# bpod_stepper_1_3.net
KiCad netlist of a schematic drawn in EAGLE
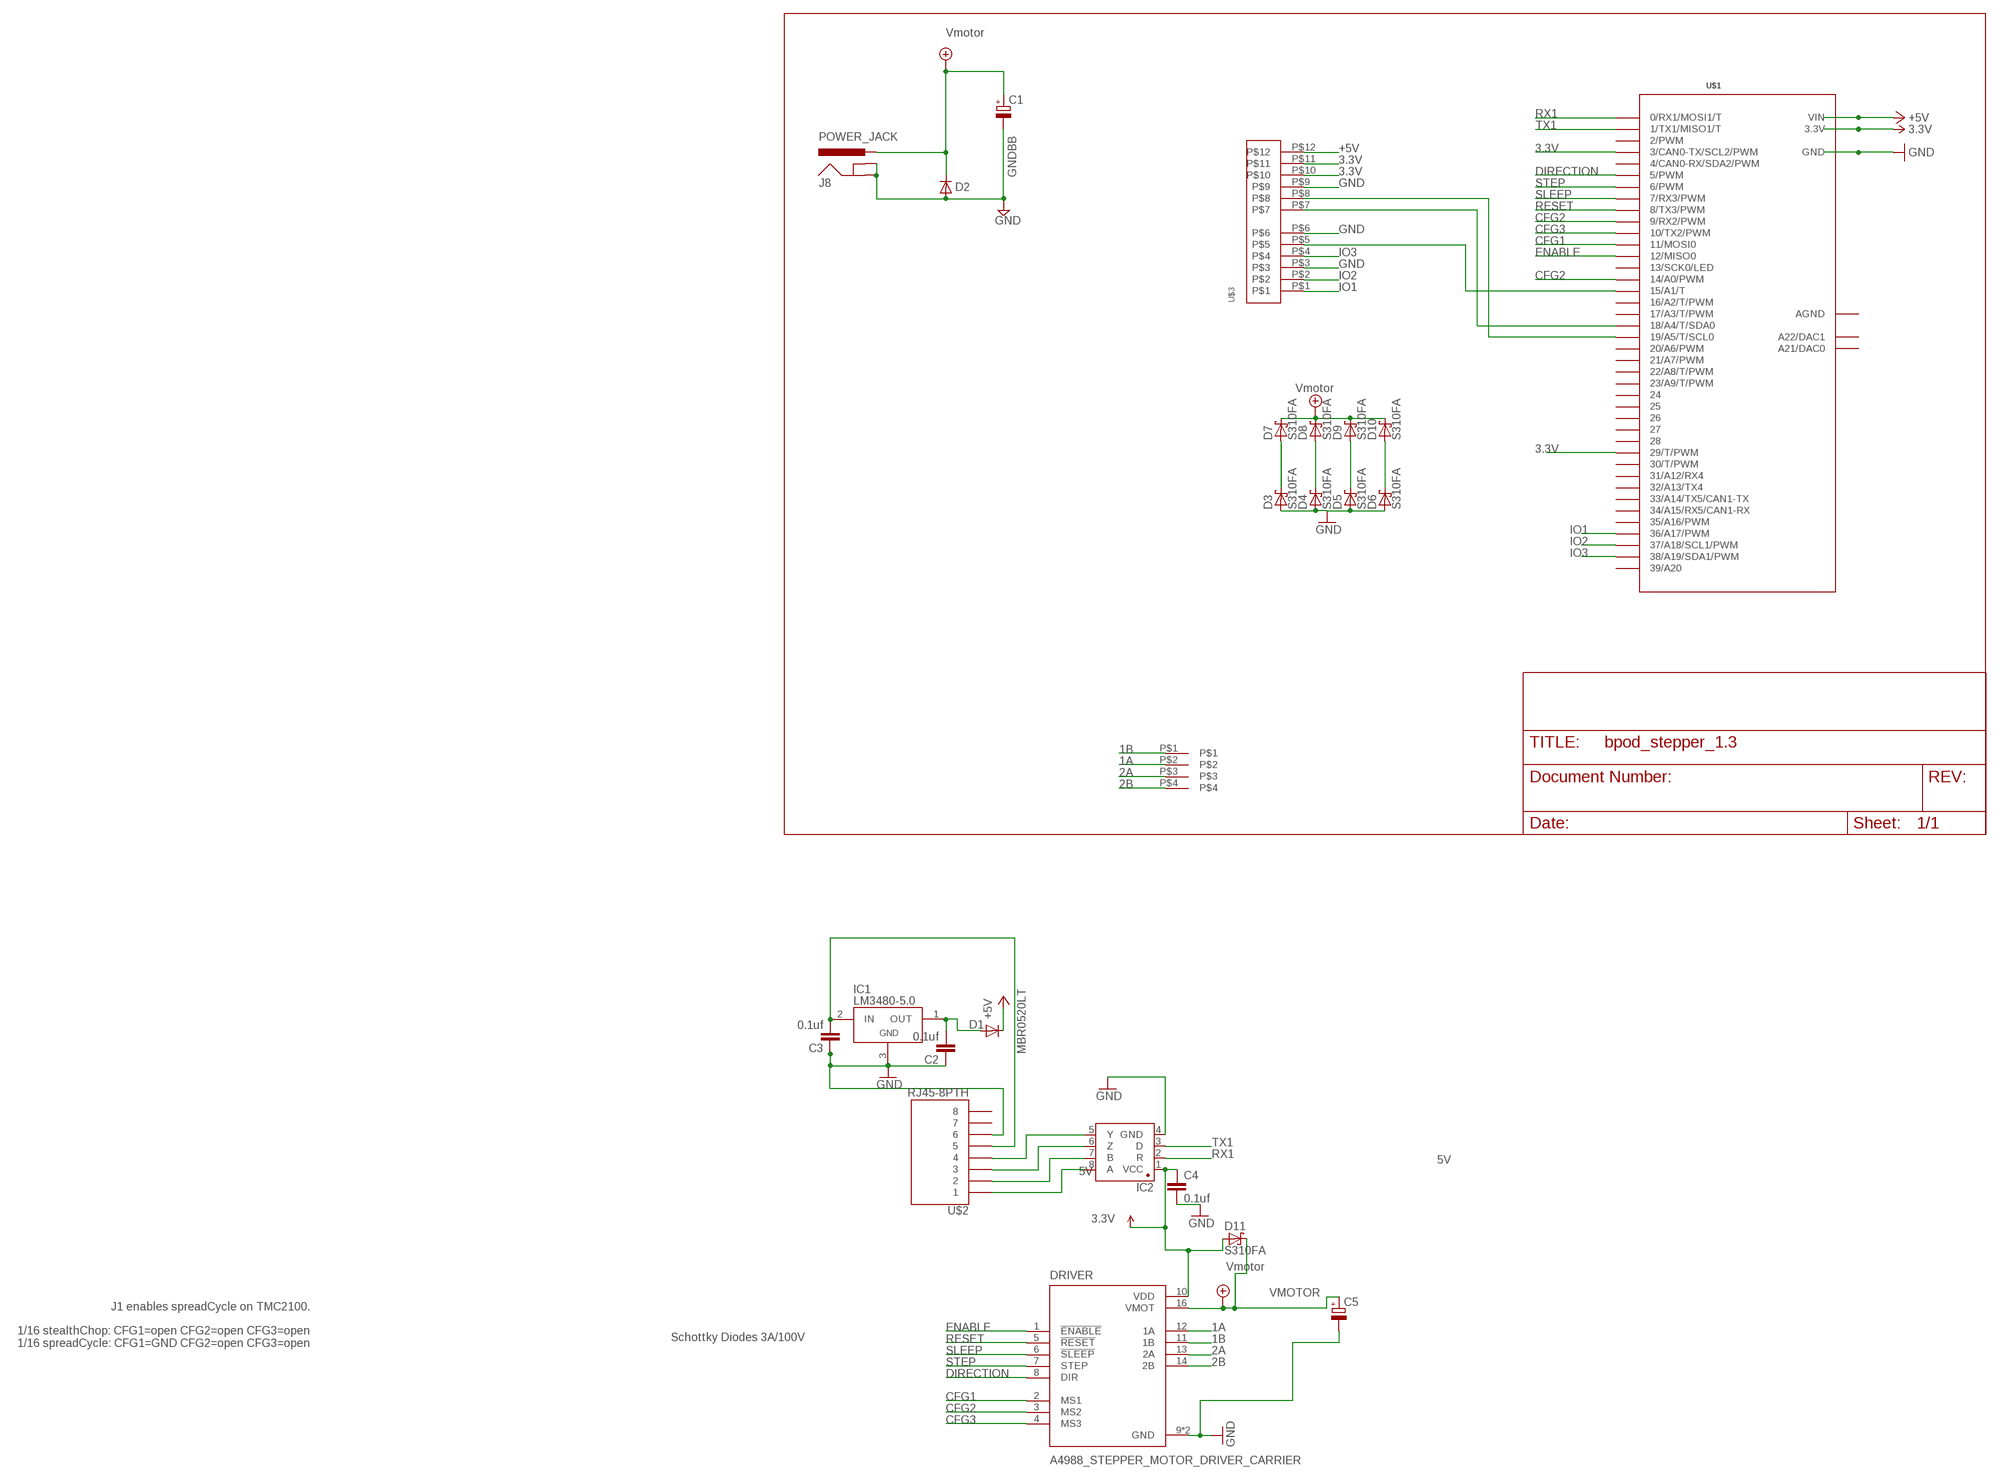
[diagram p0: schematic, sheet 1]

(export (version "E")
  (design (tool "Eeschema 10.0.6"))
  (components
    (comp (ref "C1")
      (value "CPOL-EUG")
      (footprint "eagle-import:PANASONIC_G")
      (libsource (lib "eagle-import") (part "CPOL-EUG"))
    )
    (comp (ref "C2")
      (value "0.1uf")
      (footprint "eagle-import:1206@1")
      (libsource (lib "eagle-import") (part "CAP1206"))
    )
    (comp (ref "C3")
      (value "0.1uf")
      (footprint "eagle-import:1206@1")
      (libsource (lib "eagle-import") (part "CAP1206"))
    )
    (comp (ref "C4")
      (value "0.1uf")
      (footprint "eagle-import:1206@1")
      (libsource (lib "eagle-import") (part "CAP1206"))
    )
    (comp (ref "C5")
      (value "CPOL-EUG")
      (footprint "eagle-import:PANASONIC_G")
      (libsource (lib "eagle-import") (part "CPOL-EUG"))
    )
    (comp (ref "D1")
      (value "MBR0520LT")
      (footprint "eagle-import:SOD123")
      (libsource (lib "eagle-import") (part "MBR0520LT"))
    )
    (comp (ref "D2")
      (value "DIODE-DO214AA")
      (footprint "eagle-import:DO214AA")
      (libsource (lib "eagle-import") (part "DIODE-DO214AA"))
    )
    (comp (ref "D3")
      (value "S310FA")
      (footprint "eagle-import:SOD123")
      (libsource (lib "eagle-import") (part "D_SCHOTTKY-SOD123"))
    )
    (comp (ref "D4")
      (value "S310FA")
      (footprint "eagle-import:SOD123")
      (libsource (lib "eagle-import") (part "D_SCHOTTKY-SOD123"))
    )
    (comp (ref "D5")
      (value "S310FA")
      (footprint "eagle-import:SOD123")
      (libsource (lib "eagle-import") (part "D_SCHOTTKY-SOD123"))
    )
    (comp (ref "D6")
      (value "S310FA")
      (footprint "eagle-import:SOD123")
      (libsource (lib "eagle-import") (part "D_SCHOTTKY-SOD123"))
    )
    (comp (ref "D7")
      (value "S310FA")
      (footprint "eagle-import:SOD123")
      (libsource (lib "eagle-import") (part "D_SCHOTTKY-SOD123"))
    )
    (comp (ref "D8")
      (value "S310FA")
      (footprint "eagle-import:SOD123")
      (libsource (lib "eagle-import") (part "D_SCHOTTKY-SOD123"))
    )
    (comp (ref "D9")
      (value "S310FA")
      (footprint "eagle-import:SOD123")
      (libsource (lib "eagle-import") (part "D_SCHOTTKY-SOD123"))
    )
    (comp (ref "D10")
      (value "S310FA")
      (footprint "eagle-import:SOD123")
      (libsource (lib "eagle-import") (part "D_SCHOTTKY-SOD123"))
    )
    (comp (ref "D11")
      (value "S310FA")
      (footprint "eagle-import:SOD123")
      (libsource (lib "eagle-import") (part "D_SCHOTTKY-SOD123"))
    )
    (comp (ref "DRIVER")
      (value "A4988_STEPPER_MOTOR_DRIVER_CARRIER")
      (footprint "eagle-import:MODULE_A4988_STEPPER_MOTOR_DRIVER_CARRIER")
      (fields (field (name "MF") "Pololu") (field (name "MP") "A4988 STEPPER MOTOR DRIVER CARRIER"))
      (libsource (lib "eagle-import") (part "A4988_STEPPER_MOTOR_DRIVER_CARRIER"))
    )
    (comp (ref "IC1")
      (value "LM3480-5.0")
      (footprint "eagle-import:SOT-23-3")
      (libsource (lib "eagle-import") (part "LM3480-5.0"))
    )
    (comp (ref "IC2")
      (value "SN65HVD31DR")
      (footprint "eagle-import:SO08")
      (libsource (lib "eagle-import") (part "SN65HVD31DR"))
    )
    (comp (ref "J8")
      (value "POWER_JACK")
      (footprint "eagle-import:POWER_JACK_PTH")
      (libsource (lib "eagle-import") (part "POWER_JACK"))
    )
    (comp (ref "U$1")
      (value "TEENSY_3.6_DIL")
      (footprint "eagle-import:TEENSY_3.6_DIL")
      (libsource (lib "eagle-import") (part "TEENSY_3.6_DIL"))
    )
    (comp (ref "U$2")
      (value "RJ45-8PTH")
      (footprint "eagle-import:RJ45-8")
      (libsource (lib "eagle-import") (part "RJ45-8PTH"))
    )
    (comp (ref "U$3")
      (value "12POS_MOLEX_SOCKET")
      (footprint "eagle-import:12POS_MOLEX_SOCKET")
      (libsource (lib "eagle-import") (part "12POS_MOLEX_SOCKET"))
    )
    (comp (ref "U$4")
      (value "MOLEX395221004")
      (footprint "eagle-import:MOLEX395221004")
      (libsource (lib "eagle-import") (part "MOLEX395221004"))
    )
  )
  (nets
    (net (code "1") (name "+5V") (class "Default")
      (node (ref "D1") (pin "C") (pinfunction "C_C") (pintype "passive"))
      (node (ref "U$1") (pin "VIN") (pinfunction "VIN_VIN") (pintype "power_in"))
      (node (ref "U$3") (pin "P$12") (pinfunction "P$12_P$12") (pintype "bidirectional"))
    )
    (net (code "2") (name "/1A") (class "Default")
      (node (ref "D4") (pin "C") (pinfunction "C_C") (pintype "passive"))
      (node (ref "D8") (pin "A") (pinfunction "A_A") (pintype "passive"))
      (node (ref "DRIVER") (pin "12") (pinfunction "1A_12") (pintype "output"))
      (node (ref "U$4") (pin "P$2") (pinfunction "P$2_P$2") (pintype "bidirectional"))
    )
    (net (code "3") (name "/1B") (class "Default")
      (node (ref "D3") (pin "C") (pinfunction "C_C") (pintype "passive"))
      (node (ref "D7") (pin "A") (pinfunction "A_A") (pintype "passive"))
      (node (ref "DRIVER") (pin "11") (pinfunction "1B_11") (pintype "output"))
      (node (ref "U$4") (pin "P$1") (pinfunction "P$1_P$1") (pintype "bidirectional"))
    )
    (net (code "4") (name "/2A") (class "Default")
      (node (ref "D5") (pin "C") (pinfunction "C_C") (pintype "passive"))
      (node (ref "D9") (pin "A") (pinfunction "A_A") (pintype "passive"))
      (node (ref "DRIVER") (pin "13") (pinfunction "2A_13") (pintype "output"))
      (node (ref "U$4") (pin "P$3") (pinfunction "P$3_P$3") (pintype "bidirectional"))
    )
    (net (code "5") (name "/2B") (class "Default")
      (node (ref "D10") (pin "A") (pinfunction "A_A") (pintype "passive"))
      (node (ref "D6") (pin "C") (pinfunction "C_C") (pintype "passive"))
      (node (ref "DRIVER") (pin "14") (pinfunction "2B_14") (pintype "output"))
      (node (ref "U$4") (pin "P$4") (pinfunction "P$4_P$4") (pintype "bidirectional"))
    )
    (net (code "6") (name "/AGND") (class "Default")
      (node (ref "U$1") (pin "AGND") (pinfunction "AGND_AGND") (pintype "power_in"))
    )
    (net (code "7") (name "/CFG1") (class "Default")
      (node (ref "DRIVER") (pin "2") (pinfunction "MS1_2") (pintype "input"))
      (node (ref "U$1") (pin "11") (pinfunction "11/MOSI0_11") (pintype "bidirectional"))
    )
    (net (code "8") (name "/CFG2") (class "Default")
      (node (ref "DRIVER") (pin "3") (pinfunction "MS2_3") (pintype "input"))
      (node (ref "U$1") (pin "14/A0") (pinfunction "14/A0/PWM_14/A0") (pintype "bidirectional"))
      (node (ref "U$1") (pin "9") (pinfunction "9/RX2/PWM_9") (pintype "bidirectional"))
    )
    (net (code "9") (name "/CFG3") (class "Default")
      (node (ref "DRIVER") (pin "4") (pinfunction "MS3_4") (pintype "input"))
      (node (ref "U$1") (pin "10") (pinfunction "10/TX2/PWM_10") (pintype "bidirectional"))
    )
    (net (code "10") (name "/DIRECTION") (class "Default")
      (node (ref "DRIVER") (pin "8") (pinfunction "DIR_8") (pintype "input"))
      (node (ref "U$1") (pin "5") (pinfunction "5/PWM_5") (pintype "bidirectional"))
    )
    (net (code "11") (name "/ENABLE") (class "Default")
      (node (ref "DRIVER") (pin "1") (pinfunction "~{ENABLE}_1") (pintype "input"))
      (node (ref "U$1") (pin "12") (pinfunction "12/MISO0_12") (pintype "bidirectional"))
    )
    (net (code "12") (name "/IO1") (class "Default")
      (node (ref "U$1") (pin "36/A17") (pinfunction "36/A17/PWM_36/A17") (pintype "bidirectional"))
      (node (ref "U$3") (pin "P$1") (pinfunction "P$1_P$1") (pintype "bidirectional"))
    )
    (net (code "13") (name "/IO2") (class "Default")
      (node (ref "U$1") (pin "37/A18") (pinfunction "37/A18/SCL1/PWM_37/A18") (pintype "bidirectional"))
      (node (ref "U$3") (pin "P$2") (pinfunction "P$2_P$2") (pintype "bidirectional"))
    )
    (net (code "14") (name "/IO3") (class "Default")
      (node (ref "U$1") (pin "38/A19") (pinfunction "38/A19/SDA1/PWM_38/A19") (pintype "bidirectional"))
      (node (ref "U$3") (pin "P$4") (pinfunction "P$4_P$4") (pintype "bidirectional"))
    )
    (net (code "15") (name "/RESET") (class "Default")
      (node (ref "DRIVER") (pin "5") (pinfunction "~{RESET}_5") (pintype "input"))
      (node (ref "U$1") (pin "8") (pinfunction "8/TX3/PWM_8") (pintype "bidirectional"))
    )
    (net (code "16") (name "/RX1") (class "Default")
      (node (ref "IC2") (pin "2") (pinfunction "R_2") (pintype "bidirectional"))
      (node (ref "U$1") (pin "0") (pinfunction "0/RX1/MOSI1/T_0") (pintype "bidirectional"))
    )
    (net (code "17") (name "/SLEEP") (class "Default")
      (node (ref "DRIVER") (pin "6") (pinfunction "~{SLEEP}_6") (pintype "input"))
      (node (ref "U$1") (pin "7") (pinfunction "7/RX3/PWM_7") (pintype "bidirectional"))
    )
    (net (code "18") (name "/STEP") (class "Default")
      (node (ref "DRIVER") (pin "7") (pinfunction "STEP_7") (pintype "input"))
      (node (ref "U$1") (pin "6") (pinfunction "6/PWM_6") (pintype "bidirectional"))
    )
    (net (code "19") (name "/TX1") (class "Default")
      (node (ref "IC2") (pin "3") (pinfunction "D_3") (pintype "bidirectional"))
      (node (ref "U$1") (pin "1") (pinfunction "1/TX1/MISO1/T_1") (pintype "bidirectional"))
    )
    (net (code "20") (name "3.3V") (class "Default")
      (node (ref "C4") (pin "1") (pinfunction "1_1") (pintype "passive"))
      (node (ref "D11") (pin "A") (pinfunction "A_A") (pintype "passive"))
      (node (ref "DRIVER") (pin "10") (pinfunction "VDD_10") (pintype "power_in"))
      (node (ref "IC2") (pin "1") (pinfunction "VCC_1") (pintype "bidirectional"))
      (node (ref "U$1") (pin "29") (pinfunction "29/T/PWM_29") (pintype "bidirectional"))
      (node (ref "U$1") (pin "3") (pinfunction "3/CAN0-TX/SCL2/PWM_3") (pintype "bidirectional"))
      (node (ref "U$1") (pin "3.3V") (pinfunction "3.3V_3.3V") (pintype "power_in"))
      (node (ref "U$1") (pin "3.3V3") (pinfunction "3.3V_3.3V3") (pintype "power_in"))
      (node (ref "U$3") (pin "P$10") (pinfunction "P$10_P$10") (pintype "bidirectional"))
      (node (ref "U$3") (pin "P$11") (pinfunction "P$11_P$11") (pintype "bidirectional"))
    )
    (net (code "21") (name "GND") (class "Default")
      (node (ref "C1") (pin "-") (pinfunction "-_-") (pintype "passive"))
      (node (ref "C2") (pin "1") (pinfunction "1_1") (pintype "passive"))
      (node (ref "C3") (pin "1") (pinfunction "1_1") (pintype "passive"))
      (node (ref "C4") (pin "2") (pinfunction "2_2") (pintype "passive"))
      (node (ref "C5") (pin "-") (pinfunction "-_-") (pintype "passive"))
      (node (ref "D2") (pin "A") (pinfunction "A_A") (pintype "passive"))
      (node (ref "D3") (pin "A") (pinfunction "A_A") (pintype "passive"))
      (node (ref "D4") (pin "A") (pinfunction "A_A") (pintype "passive"))
      (node (ref "D5") (pin "A") (pinfunction "A_A") (pintype "passive"))
      (node (ref "D6") (pin "A") (pinfunction "A_A") (pintype "passive"))
      (node (ref "DRIVER") (pin "15") (pinfunction "GND_15") (pintype "power_in"))
      (node (ref "DRIVER") (pin "9") (pinfunction "GND_9") (pintype "power_in"))
      (node (ref "IC1") (pin "3") (pinfunction "GND_3") (pintype "power_in"))
      (node (ref "IC2") (pin "4") (pinfunction "GND_4") (pintype "bidirectional"))
      (node (ref "J8") (pin "GND") (pinfunction "GND_GND") (pintype "bidirectional"))
      (node (ref "J8") (pin "GNDBREAK") (pinfunction "GNDBREAK_GNDBREAK") (pintype "bidirectional"))
      (node (ref "U$1") (pin "GND") (pinfunction "GND_GND") (pintype "power_in"))
      (node (ref "U$1") (pin "GND1") (pinfunction "GND_GND1") (pintype "power_in"))
      (node (ref "U$2") (pin "6") (pinfunction "6_6") (pintype "bidirectional"))
      (node (ref "U$3") (pin "P$3") (pinfunction "P$3_P$3") (pintype "bidirectional"))
      (node (ref "U$3") (pin "P$6") (pinfunction "P$6_P$6") (pintype "bidirectional"))
      (node (ref "U$3") (pin "P$9") (pinfunction "P$9_P$9") (pintype "bidirectional"))
    )
    (net (code "22") (name "Net-(IC1-IN)") (class "Default")
      (node (ref "C3") (pin "2") (pinfunction "2_2") (pintype "passive"))
      (node (ref "IC1") (pin "2") (pinfunction "IN_2") (pintype "power_in"))
      (node (ref "U$2") (pin "5") (pinfunction "5_5") (pintype "bidirectional"))
    )
    (net (code "23") (name "Net-(IC1-OUT)") (class "Default")
      (node (ref "C2") (pin "2") (pinfunction "2_2") (pintype "passive"))
      (node (ref "D1") (pin "A") (pinfunction "A_A") (pintype "passive"))
      (node (ref "IC1") (pin "1") (pinfunction "OUT_1") (pintype "power_in"))
    )
    (net (code "24") (name "Net-(IC2-A)") (class "Default")
      (node (ref "IC2") (pin "8") (pinfunction "A_8") (pintype "bidirectional"))
      (node (ref "U$2") (pin "1") (pinfunction "1_1") (pintype "bidirectional"))
    )
    (net (code "25") (name "Net-(IC2-B)") (class "Default")
      (node (ref "IC2") (pin "7") (pinfunction "B_7") (pintype "bidirectional"))
      (node (ref "U$2") (pin "2") (pinfunction "2_2") (pintype "bidirectional"))
    )
    (net (code "26") (name "Net-(IC2-Y)") (class "Default")
      (node (ref "IC2") (pin "5") (pinfunction "Y_5") (pintype "bidirectional"))
      (node (ref "U$2") (pin "4") (pinfunction "4_4") (pintype "bidirectional"))
    )
    (net (code "27") (name "Net-(IC2-Z)") (class "Default")
      (node (ref "IC2") (pin "6") (pinfunction "Z_6") (pintype "bidirectional"))
      (node (ref "U$2") (pin "3") (pinfunction "3_3") (pintype "bidirectional"))
    )
    (net (code "28") (name "Net-(U$1-15{slash}A1{slash}T)") (class "Default")
      (node (ref "U$1") (pin "15/A1") (pinfunction "15/A1/T_15/A1") (pintype "bidirectional"))
      (node (ref "U$3") (pin "P$5") (pinfunction "P$5_P$5") (pintype "bidirectional"))
    )
    (net (code "29") (name "Net-(U$1-18{slash}A4{slash}T{slash}SDA0)") (class "Default")
      (node (ref "U$1") (pin "18/A4") (pinfunction "18/A4/T/SDA0_18/A4") (pintype "bidirectional"))
      (node (ref "U$3") (pin "P$7") (pinfunction "P$7_P$7") (pintype "bidirectional"))
    )
    (net (code "30") (name "Net-(U$1-19{slash}A5{slash}T{slash}SCL0)") (class "Default")
      (node (ref "U$1") (pin "19/A5") (pinfunction "19/A5/T/SCL0_19/A5") (pintype "bidirectional"))
      (node (ref "U$3") (pin "P$8") (pinfunction "P$8_P$8") (pintype "bidirectional"))
    )
    (net (code "31") (name "Vmotor") (class "Default")
      (node (ref "C1") (pin "+") (pinfunction "+_+") (pintype "passive"))
      (node (ref "C5") (pin "+") (pinfunction "+_+") (pintype "passive"))
      (node (ref "D10") (pin "C") (pinfunction "C_C") (pintype "passive"))
      (node (ref "D11") (pin "C") (pinfunction "C_C") (pintype "passive"))
      (node (ref "D2") (pin "C") (pinfunction "C_C") (pintype "passive"))
      (node (ref "D7") (pin "C") (pinfunction "C_C") (pintype "passive"))
      (node (ref "D8") (pin "C") (pinfunction "C_C") (pintype "passive"))
      (node (ref "D9") (pin "C") (pinfunction "C_C") (pintype "passive"))
      (node (ref "DRIVER") (pin "16") (pinfunction "VMOT_16") (pintype "power_in"))
      (node (ref "J8") (pin "PWR") (pinfunction "PWR_PWR") (pintype "bidirectional"))
    )
    (net (code "32") (name "unconnected-(U$1-2{slash}PWM-Pad2)") (class "Default")
      (node (ref "U$1") (pin "2") (pinfunction "2/PWM_2") (pintype "bidirectional"))
    )
    (net (code "33") (name "unconnected-(U$1-4{slash}CAN0-RX{slash}SDA2{slash}PWM-Pad4)") (class "Default")
      (node (ref "U$1") (pin "4") (pinfunction "4/CAN0-RX/SDA2/PWM_4") (pintype "bidirectional"))
    )
    (net (code "34") (name "unconnected-(U$1-13{slash}SCK0{slash}LED-Pad13)") (class "Default")
      (node (ref "U$1") (pin "13") (pinfunction "13/SCK0/LED_13") (pintype "bidirectional"))
    )
    (net (code "35") (name "unconnected-(U$1-16{slash}A2{slash}T{slash}PWM-Pad16{slash}A2)") (class "Default")
      (node (ref "U$1") (pin "16/A2") (pinfunction "16/A2/T/PWM_16/A2") (pintype "bidirectional"))
    )
    (net (code "36") (name "unconnected-(U$1-17{slash}A3{slash}T{slash}PWM-Pad17{slash}A3)") (class "Default")
      (node (ref "U$1") (pin "17/A3") (pinfunction "17/A3/T/PWM_17/A3") (pintype "bidirectional"))
    )
    (net (code "37") (name "unconnected-(U$1-20{slash}A6{slash}PWM-Pad20{slash}A6)") (class "Default")
      (node (ref "U$1") (pin "20/A6") (pinfunction "20/A6/PWM_20/A6") (pintype "bidirectional"))
    )
    (net (code "38") (name "unconnected-(U$1-21{slash}A7{slash}PWM-Pad21{slash}A7)") (class "Default")
      (node (ref "U$1") (pin "21/A7") (pinfunction "21/A7/PWM_21/A7") (pintype "bidirectional"))
    )
    (net (code "39") (name "unconnected-(U$1-22{slash}A8{slash}T{slash}PWM-Pad22{slash}A8)") (class "Default")
      (node (ref "U$1") (pin "22/A8") (pinfunction "22/A8/T/PWM_22/A8") (pintype "bidirectional"))
    )
    (net (code "40") (name "unconnected-(U$1-23{slash}A9{slash}T{slash}PWM-Pad23{slash}A9)") (class "Default")
      (node (ref "U$1") (pin "23/A9") (pinfunction "23/A9/T/PWM_23/A9") (pintype "bidirectional"))
    )
    (net (code "41") (name "unconnected-(U$1-30{slash}T{slash}PWM-Pad30)") (class "Default")
      (node (ref "U$1") (pin "30") (pinfunction "30/T/PWM_30") (pintype "bidirectional"))
    )
    (net (code "42") (name "unconnected-(U$1-31{slash}A12{slash}RX4-Pad31{slash}A12)") (class "Default")
      (node (ref "U$1") (pin "31/A12") (pinfunction "31/A12/RX4_31/A12") (pintype "bidirectional"))
    )
    (net (code "43") (name "unconnected-(U$1-32{slash}A13{slash}TX4-Pad32{slash}A13)") (class "Default")
      (node (ref "U$1") (pin "32/A13") (pinfunction "32/A13/TX4_32/A13") (pintype "bidirectional"))
    )
    (net (code "44") (name "unconnected-(U$1-33{slash}A14{slash}TX5{slash}CAN1-TX-Pad33{slash}A14)") (class "Default")
      (node (ref "U$1") (pin "33/A14") (pinfunction "33/A14/TX5/CAN1-TX_33/A14") (pintype "bidirectional"))
    )
    (net (code "45") (name "unconnected-(U$1-34{slash}A15{slash}RX5{slash}CAN1-RX-Pad34{slash}A15)") (class "Default")
      (node (ref "U$1") (pin "34/A15") (pinfunction "34/A15/RX5/CAN1-RX_34/A15") (pintype "bidirectional"))
    )
    (net (code "46") (name "unconnected-(U$1-35{slash}A16{slash}PWM-Pad35{slash}A16)") (class "Default")
      (node (ref "U$1") (pin "35/A16") (pinfunction "35/A16/PWM_35/A16") (pintype "bidirectional"))
    )
    (net (code "47") (name "unconnected-(U$1-A21{slash}DAC0-PadA21)") (class "Default")
      (node (ref "U$1") (pin "A21") (pinfunction "A21/DAC0_A21") (pintype "bidirectional"))
    )
    (net (code "48") (name "unconnected-(U$1-A22{slash}DAC1-PadA22)") (class "Default")
      (node (ref "U$1") (pin "A22") (pinfunction "A22/DAC1_A22") (pintype "bidirectional"))
    )
    (net (code "49") (name "unconnected-(U$1-Pad24)") (class "Default")
      (node (ref "U$1") (pin "24") (pinfunction "24_24") (pintype "bidirectional"))
    )
    (net (code "50") (name "unconnected-(U$1-Pad25)") (class "Default")
      (node (ref "U$1") (pin "25") (pinfunction "25_25") (pintype "bidirectional"))
    )
    (net (code "51") (name "unconnected-(U$1-Pad26)") (class "Default")
      (node (ref "U$1") (pin "26") (pinfunction "26_26") (pintype "bidirectional"))
    )
    (net (code "52") (name "unconnected-(U$1-Pad27)") (class "Default")
      (node (ref "U$1") (pin "27") (pinfunction "27_27") (pintype "bidirectional"))
    )
    (net (code "53") (name "unconnected-(U$1-Pad28)") (class "Default")
      (node (ref "U$1") (pin "28") (pinfunction "28_28") (pintype "bidirectional"))
    )
    (net (code "54") (name "unconnected-(U$1-Pad39{slash}A20)") (class "Default")
      (node (ref "U$1") (pin "39/A20") (pinfunction "39/A20_39/A20") (pintype "bidirectional"))
    )
    (net (code "55") (name "unconnected-(U$2-Pad7)") (class "Default")
      (node (ref "U$2") (pin "7") (pinfunction "7_7") (pintype "bidirectional"))
    )
    (net (code "56") (name "unconnected-(U$2-Pad8)") (class "Default")
      (node (ref "U$2") (pin "8") (pinfunction "8_8") (pintype "bidirectional"))
    )
  )
)
